# ATmega128RFA1-DevBoard.net
KiCad netlist of a schematic drawn in EAGLE
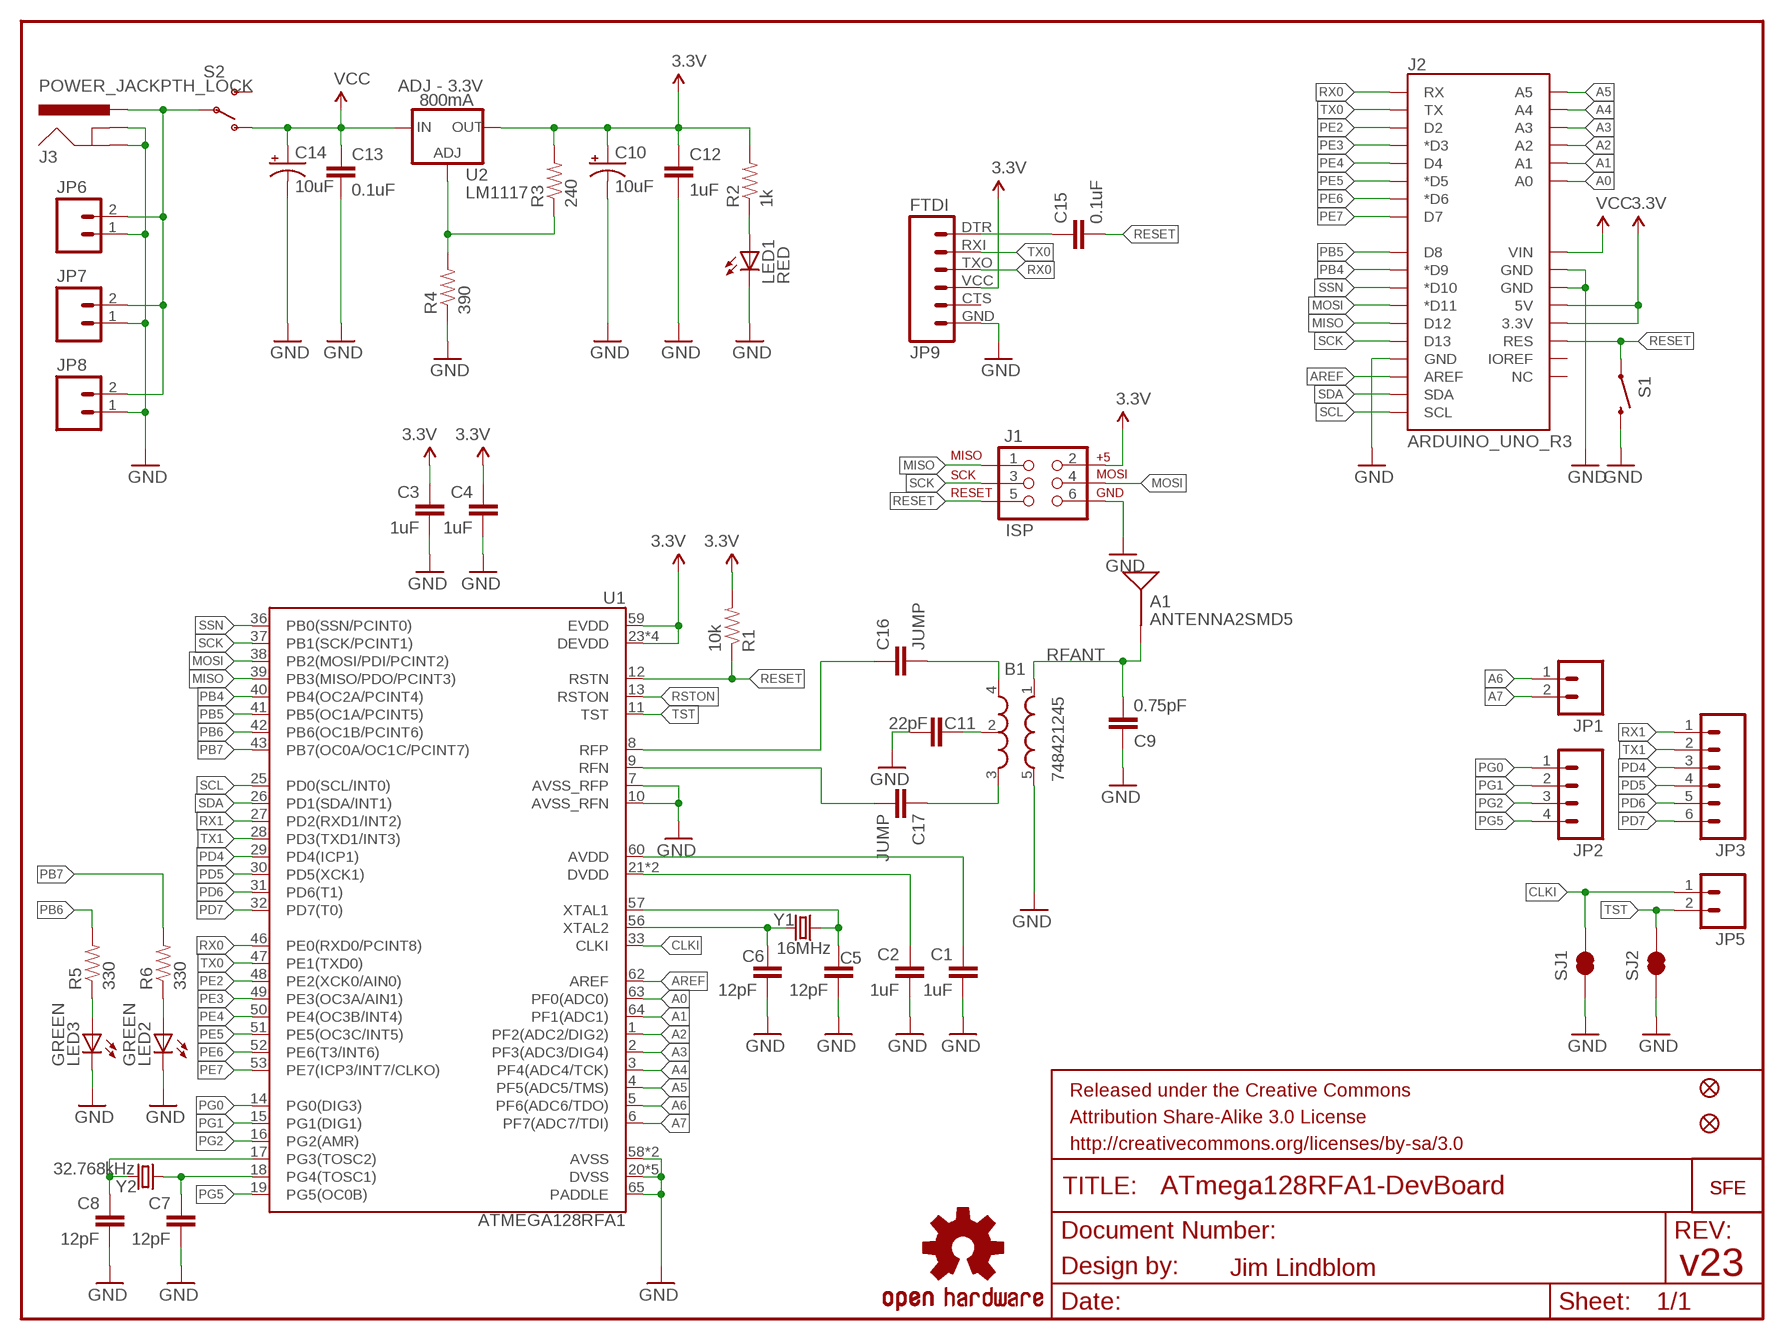
[diagram p0: schematic, sheet 1]

(export (version "E")
  (design (tool "Eeschema 10.0.6"))
  (components
    (comp (ref "A1")
      (value "ANTENNA2SMD5")
      (footprint "eagle-import:ANTENNA-CHIP5")
      (libsource (lib "eagle-import") (part "ANTENNA2SMD5"))
    )
    (comp (ref "B1")
      (value "748421245")
      (footprint "eagle-import:BALUN")
      (libsource (lib "eagle-import") (part "BALUN0805"))
    )
    (comp (ref "C1")
      (value "1uF")
      (footprint "eagle-import:0402-CAP")
      (libsource (lib "eagle-import") (part "SparkFun-Passives_CAP0402-CAP"))
    )
    (comp (ref "C2")
      (value "1uF")
      (footprint "eagle-import:0402-CAP")
      (libsource (lib "eagle-import") (part "SparkFun-Passives_CAP0402-CAP"))
    )
    (comp (ref "C3")
      (value "1uF")
      (footprint "eagle-import:0402-CAP")
      (libsource (lib "eagle-import") (part "SparkFun-Passives_CAP0402-CAP"))
    )
    (comp (ref "C4")
      (value "1uF")
      (footprint "eagle-import:0402-CAP")
      (libsource (lib "eagle-import") (part "SparkFun-Passives_CAP0402-CAP"))
    )
    (comp (ref "C5")
      (value "12pF")
      (footprint "eagle-import:0402-CAP")
      (libsource (lib "eagle-import") (part "SparkFun-Passives_CAP0402-CAP"))
    )
    (comp (ref "C6")
      (value "12pF")
      (footprint "eagle-import:0402-CAP")
      (libsource (lib "eagle-import") (part "SparkFun-Passives_CAP0402-CAP"))
    )
    (comp (ref "C7")
      (value "12pF")
      (footprint "eagle-import:0402-CAP")
      (libsource (lib "eagle-import") (part "SparkFun-Passives_CAP0402-CAP"))
    )
    (comp (ref "C8")
      (value "12pF")
      (footprint "eagle-import:0402-CAP")
      (libsource (lib "eagle-import") (part "SparkFun-Passives_CAP0402-CAP"))
    )
    (comp (ref "C9")
      (value "0.75pF")
      (footprint "eagle-import:0402-CAP")
      (libsource (lib "eagle-import") (part "SparkFun-Passives_CAP0402-CAP"))
    )
    (comp (ref "C10")
      (value "10uF")
      (footprint "eagle-import:EIA3216")
      (libsource (lib "eagle-import") (part "CAP_POL1206"))
    )
    (comp (ref "C11")
      (value "22pF")
      (footprint "eagle-import:0402-CAP")
      (libsource (lib "eagle-import") (part "SparkFun-Passives_CAP0402-CAP"))
    )
    (comp (ref "C12")
      (value "1uF")
      (footprint "eagle-import:0402-CAP")
      (libsource (lib "eagle-import") (part "SparkFun-Passives_CAP0402-CAP"))
    )
    (comp (ref "C13")
      (value "0.1uF")
      (footprint "eagle-import:0402-CAP")
      (libsource (lib "eagle-import") (part "SparkFun-Passives_CAP0402-CAP"))
    )
    (comp (ref "C14")
      (value "10uF")
      (footprint "eagle-import:EIA3216")
      (libsource (lib "eagle-import") (part "CAP_POL1206"))
    )
    (comp (ref "C15")
      (value "0.1uF")
      (footprint "eagle-import:0402-CAP")
      (libsource (lib "eagle-import") (part "SparkFun-Passives_CAP0402-CAP"))
    )
    (comp (ref "C16")
      (value "JUMP")
      (footprint "eagle-import:0402-CAP")
      (libsource (lib "eagle-import") (part "CAP0402-CAP"))
    )
    (comp (ref "C17")
      (value "JUMP")
      (footprint "eagle-import:0402-CAP")
      (libsource (lib "eagle-import") (part "CAP0402-CAP"))
    )
    (comp (ref "FID1")
      (value "FIDUCIALUFIDUCIAL")
      (footprint "eagle-import:MICRO-FIDUCIAL")
      (libsource (lib "eagle-import") (part "FIDUCIALUFIDUCIAL"))
    )
    (comp (ref "FID2")
      (value "FIDUCIALUFIDUCIAL")
      (footprint "eagle-import:MICRO-FIDUCIAL")
      (libsource (lib "eagle-import") (part "FIDUCIALUFIDUCIAL"))
    )
    (comp (ref "J1")
      (value "ISP")
      (footprint "eagle-import:2X3-NS")
      (libsource (lib "eagle-import") (part "AVR_SPI_PRG_6NS"))
    )
    (comp (ref "J2")
      (value "ARDUINO_UNO_R3")
      (footprint "eagle-import:ARDUINO_UNO_R3")
      (libsource (lib "eagle-import") (part "ARDUINO_UNO_R3"))
    )
    (comp (ref "J3")
      (value "POWER_JACKPTH_LOCK")
      (footprint "eagle-import:POWER_JACK_PTH_LOCK")
      (libsource (lib "eagle-import") (part "POWER_JACKPTH_LOCK"))
    )
    (comp (ref "JP1")
      (value "M021X02_NO_SILK")
      (footprint "eagle-import:1X02_NO_SILK")
      (libsource (lib "eagle-import") (part "M021X02_NO_SILK"))
    )
    (comp (ref "JP2")
      (value "M041X04_NO_SILK")
      (footprint "eagle-import:1X04_NO_SILK")
      (libsource (lib "eagle-import") (part "M041X04_NO_SILK"))
    )
    (comp (ref "JP3")
      (value "M06SIP-NS")
      (footprint "eagle-import:1X06_NS")
      (libsource (lib "eagle-import") (part "M06SIP-NS"))
    )
    (comp (ref "JP4")
      (value "LOGO-SFENEW")
      (footprint "eagle-import:SFE-NEW-WEBLOGO")
      (libsource (lib "eagle-import") (part "LOGO-SFENEW"))
    )
    (comp (ref "JP5")
      (value "M021X02_NO_SILK")
      (footprint "eagle-import:1X02_NO_SILK")
      (libsource (lib "eagle-import") (part "M021X02_NO_SILK"))
    )
    (comp (ref "JP6")
      (value "M02JST-PTH-2")
      (footprint "eagle-import:JST-2-PTH")
      (libsource (lib "eagle-import") (part "M02JST-PTH-2"))
    )
    (comp (ref "JP7")
      (value "M021X02_NO_SILK")
      (footprint "eagle-import:1X02_NO_SILK")
      (libsource (lib "eagle-import") (part "M021X02_NO_SILK"))
    )
    (comp (ref "JP8")
      (value "M023.5MM-NO_SILK")
      (footprint "eagle-import:SCREWTERMINAL-3.5MM-2-NS")
      (libsource (lib "eagle-import") (part "M023.5MM-NO_SILK"))
    )
    (comp (ref "JP9")
      (value "FTDI")
      (footprint "eagle-import:FTDI_BASIC")
      (libsource (lib "eagle-import") (part "FTDI_BASICPTH"))
    )
    (comp (ref "JP10")
      (value "LOGO-SFENEW")
      (footprint "eagle-import:SFE-NEW-WEBLOGO")
      (libsource (lib "eagle-import") (part "LOGO-SFENEW"))
    )
    (comp (ref "LED1")
      (value "RED")
      (footprint "eagle-import:LED-0603")
      (libsource (lib "eagle-import") (part "LED0603"))
    )
    (comp (ref "LED2")
      (value "GREEN")
      (footprint "eagle-import:LED-0603")
      (libsource (lib "eagle-import") (part "LED0603"))
    )
    (comp (ref "LED3")
      (value "GREEN")
      (footprint "eagle-import:LED-0603")
      (libsource (lib "eagle-import") (part "LED0603"))
    )
    (comp (ref "R1")
      (value "10k")
      (footprint "eagle-import:0402-RES")
      (libsource (lib "eagle-import") (part "SparkFun-Passives_RESISTOR0402-RES"))
    )
    (comp (ref "R2")
      (value "1k")
      (footprint "eagle-import:0402-RES")
      (libsource (lib "eagle-import") (part "SparkFun-Passives_RESISTOR0402-RES"))
    )
    (comp (ref "R3")
      (value "240")
      (footprint "eagle-import:0402-RES")
      (libsource (lib "eagle-import") (part "RESISTOR0402-RES"))
    )
    (comp (ref "R4")
      (value "390")
      (footprint "eagle-import:0402-RES")
      (libsource (lib "eagle-import") (part "RESISTOR0402-RES"))
    )
    (comp (ref "R5")
      (value "330")
      (footprint "eagle-import:0402-RES")
      (libsource (lib "eagle-import") (part "RESISTOR0402-RES"))
    )
    (comp (ref "R6")
      (value "330")
      (footprint "eagle-import:0402-RES")
      (libsource (lib "eagle-import") (part "RESISTOR0402-RES"))
    )
    (comp (ref "S1")
      (value "SWITCH-MOMENTARY-2SMD")
      (footprint "eagle-import:TACTILE_SWITCH_SMD")
      (libsource (lib "eagle-import") (part "SWITCH-MOMENTARY-2SMD"))
    )
    (comp (ref "S2")
      (value "SWITCH-SPST-SMD-A")
      (footprint "eagle-import:SWITCH-SPST-SMD-A")
      (libsource (lib "eagle-import") (part "SWITCH-SPST-SMD-A"))
    )
    (comp (ref "SJ1")
      (value "SOLDERJUMPERTRACE")
      (footprint "eagle-import:SJ_2S-TRACE")
      (libsource (lib "eagle-import") (part "SOLDERJUMPERTRACE"))
    )
    (comp (ref "SJ2")
      (value "SOLDERJUMPERTRACE")
      (footprint "eagle-import:SJ_2S-TRACE")
      (libsource (lib "eagle-import") (part "SOLDERJUMPERTRACE"))
    )
    (comp (ref "U$1")
      (value "OSHW-LOGOS")
      (footprint "eagle-import:OSHW-LOGO-S")
      (libsource (lib "eagle-import") (part "OSHW-LOGOS"))
    )
    (comp (ref "U1")
      (value "ATMEGA128RFA1")
      (footprint "eagle-import:QFN-64")
      (libsource (lib "eagle-import") (part "ATMEGA128RFA1"))
    )
    (comp (ref "U2")
      (value "LM1117")
      (footprint "eagle-import:SOT223")
      (libsource (lib "eagle-import") (part "V_REG_317SMD"))
    )
    (comp (ref "Y1")
      (value "16MHz")
      (footprint "eagle-import:CRYSTAL-SMD-5X3")
      (libsource (lib "eagle-import") (part "CRYSTAL5X3"))
    )
    (comp (ref "Y2")
      (value "32.768kHz")
      (footprint "eagle-import:CRYSTAL-32KHZ-SMD")
      (libsource (lib "eagle-import") (part "CRYSTAL32-SMD"))
    )
  )
  (nets
    (net (code "1") (name "/RFANT") (class "Default")
      (node (ref "A1") (pin "FEED") (pinfunction "SIGNAL_FEED") (pintype "bidirectional"))
      (node (ref "B1") (pin "1") (pinfunction "IN_1") (pintype "bidirectional"))
      (node (ref "C9") (pin "2") (pinfunction "2_2") (pintype "passive"))
    )
    (net (code "2") (name "3.3V") (class "Default")
      (node (ref "C10") (pin "A") (pinfunction "+_A") (pintype "passive"))
      (node (ref "C12") (pin "1") (pinfunction "1_1") (pintype "passive"))
      (node (ref "C3") (pin "1") (pinfunction "1_1") (pintype "passive"))
      (node (ref "C4") (pin "1") (pinfunction "1_1") (pintype "passive"))
      (node (ref "J1") (pin "2") (pinfunction "2_2") (pintype "passive"))
      (node (ref "J2") (pin "3.3V") (pinfunction "3.3V_3.3V") (pintype "bidirectional"))
      (node (ref "J2") (pin "5V") (pinfunction "5V_5V") (pintype "bidirectional"))
      (node (ref "JP9") (pin "VCC") (pinfunction "4_VCC") (pintype "passive"))
      (node (ref "R1") (pin "2") (pinfunction "2_2") (pintype "passive"))
      (node (ref "R2") (pin "2") (pinfunction "2_2") (pintype "passive"))
      (node (ref "R3") (pin "2") (pinfunction "2_2") (pintype "passive"))
      (node (ref "U1") (pin "23") (pinfunction "DEVDD_23") (pintype "bidirectional"))
      (node (ref "U1") (pin "34") (pinfunction "DEVDD_34") (pintype "bidirectional"))
      (node (ref "U1") (pin "44") (pinfunction "DEVDD_44") (pintype "bidirectional"))
      (node (ref "U1") (pin "54") (pinfunction "DEVDD_54") (pintype "bidirectional"))
      (node (ref "U1") (pin "59") (pinfunction "EVDD_59") (pintype "bidirectional"))
      (node (ref "U2") (pin "2") (pinfunction "OUT_2") (pintype "output"))
    )
    (net (code "3") (name "A0") (class "Default")
      (node (ref "J2") (pin "A0") (pinfunction "A0_A0") (pintype "bidirectional"))
      (node (ref "U1") (pin "63") (pinfunction "PF0(ADC0)_63") (pintype "bidirectional"))
    )
    (net (code "4") (name "A1") (class "Default")
      (node (ref "J2") (pin "A1") (pinfunction "A1_A1") (pintype "bidirectional"))
      (node (ref "U1") (pin "64") (pinfunction "PF1(ADC1)_64") (pintype "bidirectional"))
    )
    (net (code "5") (name "A2") (class "Default")
      (node (ref "J2") (pin "A2") (pinfunction "A2_A2") (pintype "bidirectional"))
      (node (ref "U1") (pin "1") (pinfunction "PF2(ADC2/DIG2)_1") (pintype "bidirectional"))
    )
    (net (code "6") (name "A3") (class "Default")
      (node (ref "J2") (pin "A3") (pinfunction "A3_A3") (pintype "bidirectional"))
      (node (ref "U1") (pin "2") (pinfunction "PF3(ADC3/DIG4)_2") (pintype "bidirectional"))
    )
    (net (code "7") (name "A4") (class "Default")
      (node (ref "J2") (pin "A4") (pinfunction "A4_A4") (pintype "bidirectional"))
      (node (ref "U1") (pin "3") (pinfunction "PF4(ADC4/TCK)_3") (pintype "bidirectional"))
    )
    (net (code "8") (name "A5") (class "Default")
      (node (ref "J2") (pin "A5") (pinfunction "A5_A5") (pintype "bidirectional"))
      (node (ref "U1") (pin "4") (pinfunction "PF5(ADC5/TMS)_4") (pintype "bidirectional"))
    )
    (net (code "9") (name "A6") (class "Default")
      (node (ref "JP1") (pin "1") (pinfunction "1_1") (pintype "passive"))
      (node (ref "U1") (pin "5") (pinfunction "PF6(ADC6/TDO)_5") (pintype "bidirectional"))
    )
    (net (code "10") (name "A7") (class "Default")
      (node (ref "JP1") (pin "2") (pinfunction "2_2") (pintype "passive"))
      (node (ref "U1") (pin "6") (pinfunction "PF7(ADC7/TDI)_6") (pintype "bidirectional"))
    )
    (net (code "11") (name "AREF") (class "Default")
      (node (ref "J2") (pin "AREF") (pinfunction "AREF_AREF") (pintype "bidirectional"))
      (node (ref "U1") (pin "62") (pinfunction "AREF_62") (pintype "bidirectional"))
    )
    (net (code "12") (name "CLKI") (class "Default")
      (node (ref "JP5") (pin "1") (pinfunction "1_1") (pintype "passive"))
      (node (ref "SJ1") (pin "2") (pinfunction "2_2") (pintype "passive"))
      (node (ref "U1") (pin "33") (pinfunction "CLKI_33") (pintype "bidirectional"))
    )
    (net (code "13") (name "GND") (class "Default")
      (node (ref "B1") (pin "5") (pinfunction "GND_5") (pintype "bidirectional"))
      (node (ref "C1") (pin "2") (pinfunction "2_2") (pintype "passive"))
      (node (ref "C10") (pin "C") (pinfunction "-_C") (pintype "passive"))
      (node (ref "C11") (pin "2") (pinfunction "2_2") (pintype "passive"))
      (node (ref "C12") (pin "2") (pinfunction "2_2") (pintype "passive"))
      (node (ref "C13") (pin "2") (pinfunction "2_2") (pintype "passive"))
      (node (ref "C14") (pin "C") (pinfunction "-_C") (pintype "passive"))
      (node (ref "C2") (pin "2") (pinfunction "2_2") (pintype "passive"))
      (node (ref "C3") (pin "2") (pinfunction "2_2") (pintype "passive"))
      (node (ref "C4") (pin "2") (pinfunction "2_2") (pintype "passive"))
      (node (ref "C5") (pin "2") (pinfunction "2_2") (pintype "passive"))
      (node (ref "C6") (pin "2") (pinfunction "2_2") (pintype "passive"))
      (node (ref "C7") (pin "2") (pinfunction "2_2") (pintype "passive"))
      (node (ref "C8") (pin "2") (pinfunction "2_2") (pintype "passive"))
      (node (ref "C9") (pin "1") (pinfunction "1_1") (pintype "passive"))
      (node (ref "J1") (pin "6") (pinfunction "6_6") (pintype "passive"))
      (node (ref "J2") (pin "GND@0") (pinfunction "GND_GND@0") (pintype "bidirectional"))
      (node (ref "J2") (pin "GND@1") (pinfunction "GND_GND@1") (pintype "bidirectional"))
      (node (ref "J2") (pin "GND@2") (pinfunction "GND_GND@2") (pintype "bidirectional"))
      (node (ref "J3") (pin "GND") (pinfunction "GND_GND") (pintype "bidirectional"))
      (node (ref "J3") (pin "GNDBREAK") (pinfunction "GNDBREAK_GNDBREAK") (pintype "bidirectional"))
      (node (ref "JP6") (pin "1") (pinfunction "1_1") (pintype "passive"))
      (node (ref "JP7") (pin "1") (pinfunction "1_1") (pintype "passive"))
      (node (ref "JP8") (pin "1") (pinfunction "1_1") (pintype "passive"))
      (node (ref "JP9") (pin "GND") (pinfunction "6_GND") (pintype "passive"))
      (node (ref "LED1") (pin "C") (pinfunction "C_C") (pintype "passive"))
      (node (ref "LED2") (pin "C") (pinfunction "C_C") (pintype "passive"))
      (node (ref "LED3") (pin "C") (pinfunction "C_C") (pintype "passive"))
      (node (ref "R4") (pin "1") (pinfunction "1_1") (pintype "passive"))
      (node (ref "S1") (pin "3") (pinfunction "2_3") (pintype "passive"))
      (node (ref "SJ1") (pin "1") (pinfunction "1_1") (pintype "passive"))
      (node (ref "SJ2") (pin "1") (pinfunction "1_1") (pintype "passive"))
      (node (ref "U1") (pin "10") (pinfunction "AVSS_RFN_10") (pintype "bidirectional"))
      (node (ref "U1") (pin "20") (pinfunction "DVSS_20") (pintype "bidirectional"))
      (node (ref "U1") (pin "24") (pinfunction "DVSS_24") (pintype "bidirectional"))
      (node (ref "U1") (pin "35") (pinfunction "DVSS_35") (pintype "bidirectional"))
      (node (ref "U1") (pin "45") (pinfunction "DVSS_45") (pintype "bidirectional"))
      (node (ref "U1") (pin "55") (pinfunction "DVSS_55") (pintype "bidirectional"))
      (node (ref "U1") (pin "58") (pinfunction "AVSS_58") (pintype "bidirectional"))
      (node (ref "U1") (pin "61") (pinfunction "AVSS_61") (pintype "bidirectional"))
      (node (ref "U1") (pin "65") (pinfunction "PADDLE_65") (pintype "bidirectional"))
      (node (ref "U1") (pin "7") (pinfunction "AVSS_RFP_7") (pintype "bidirectional"))
    )
    (net (code "14") (name "MISO") (class "Default")
      (node (ref "J1") (pin "1") (pinfunction "1_1") (pintype "passive"))
      (node (ref "J2") (pin "D12") (pinfunction "D12_D12") (pintype "bidirectional"))
      (node (ref "U1") (pin "39") (pinfunction "PB3(MISO/PDO/PCINT3)_39") (pintype "bidirectional"))
    )
    (net (code "15") (name "MOSI") (class "Default")
      (node (ref "J1") (pin "4") (pinfunction "4_4") (pintype "passive"))
      (node (ref "J2") (pin "D11") (pinfunction "*D11_D11") (pintype "bidirectional"))
      (node (ref "U1") (pin "38") (pinfunction "PB2(MOSI/PDI/PCINT2)_38") (pintype "bidirectional"))
    )
    (net (code "16") (name "Net-(B1-GND-Pad2)") (class "Default")
      (node (ref "B1") (pin "2") (pinfunction "GND_2") (pintype "bidirectional"))
      (node (ref "C11") (pin "1") (pinfunction "1_1") (pintype "passive"))
    )
    (net (code "17") (name "Net-(B1-OUT1)") (class "Default")
      (node (ref "B1") (pin "4") (pinfunction "OUT1_4") (pintype "bidirectional"))
      (node (ref "C16") (pin "2") (pinfunction "2_2") (pintype "passive"))
    )
    (net (code "18") (name "Net-(B1-OUT2)") (class "Default")
      (node (ref "B1") (pin "3") (pinfunction "OUT2_3") (pintype "bidirectional"))
      (node (ref "C17") (pin "1") (pinfunction "1_1") (pintype "passive"))
    )
    (net (code "19") (name "Net-(C2-Pad1)") (class "Default")
      (node (ref "C2") (pin "1") (pinfunction "1_1") (pintype "passive"))
      (node (ref "U1") (pin "21") (pinfunction "DVDD_21") (pintype "bidirectional"))
      (node (ref "U1") (pin "22") (pinfunction "DVDD_22") (pintype "bidirectional"))
    )
    (net (code "20") (name "Net-(JP9-1)") (class "Default")
      (node (ref "C15") (pin "1") (pinfunction "1_1") (pintype "passive"))
      (node (ref "JP9") (pin "DTR") (pinfunction "1_DTR") (pintype "passive"))
    )
    (net (code "21") (name "Net-(LED1-PadA)") (class "Default")
      (node (ref "LED1") (pin "A") (pinfunction "A_A") (pintype "passive"))
      (node (ref "R2") (pin "1") (pinfunction "1_1") (pintype "passive"))
    )
    (net (code "22") (name "Net-(LED2-PadA)") (class "Default")
      (node (ref "LED2") (pin "A") (pinfunction "A_A") (pintype "passive"))
      (node (ref "R6") (pin "1") (pinfunction "1_1") (pintype "passive"))
    )
    (net (code "23") (name "Net-(LED3-PadA)") (class "Default")
      (node (ref "LED3") (pin "A") (pinfunction "A_A") (pintype "passive"))
      (node (ref "R5") (pin "1") (pinfunction "1_1") (pintype "passive"))
    )
    (net (code "24") (name "Net-(S2-P)") (class "Default")
      (node (ref "J3") (pin "PWR") (pinfunction "PWR_PWR") (pintype "bidirectional"))
      (node (ref "JP6") (pin "2") (pinfunction "2_2") (pintype "passive"))
      (node (ref "JP7") (pin "2") (pinfunction "2_2") (pintype "passive"))
      (node (ref "JP8") (pin "2") (pinfunction "2_2") (pintype "passive"))
      (node (ref "S2") (pin "2") (pinfunction "P_2") (pintype "passive"))
    )
    (net (code "25") (name "Net-(U1-AVDD)") (class "Default")
      (node (ref "C1") (pin "1") (pinfunction "1_1") (pintype "passive"))
      (node (ref "U1") (pin "60") (pinfunction "AVDD_60") (pintype "bidirectional"))
    )
    (net (code "26") (name "Net-(U1-PG3(TOSC2))") (class "Default")
      (node (ref "C8") (pin "1") (pinfunction "1_1") (pintype "passive"))
      (node (ref "U1") (pin "17") (pinfunction "PG3(TOSC2)_17") (pintype "bidirectional"))
      (node (ref "Y2") (pin "X2") (pinfunction "2_X2") (pintype "passive"))
    )
    (net (code "27") (name "Net-(U1-PG4(TOSC1))") (class "Default")
      (node (ref "C7") (pin "1") (pinfunction "1_1") (pintype "passive"))
      (node (ref "U1") (pin "18") (pinfunction "PG4(TOSC1)_18") (pintype "bidirectional"))
      (node (ref "Y2") (pin "X1") (pinfunction "1_X1") (pintype "passive"))
    )
    (net (code "28") (name "Net-(U1-RFN)") (class "Default")
      (node (ref "C17") (pin "2") (pinfunction "2_2") (pintype "passive"))
      (node (ref "U1") (pin "9") (pinfunction "RFN_9") (pintype "bidirectional"))
    )
    (net (code "29") (name "Net-(U1-RFP)") (class "Default")
      (node (ref "C16") (pin "1") (pinfunction "1_1") (pintype "passive"))
      (node (ref "U1") (pin "8") (pinfunction "RFP_8") (pintype "bidirectional"))
    )
    (net (code "30") (name "Net-(U1-XTAL1)") (class "Default")
      (node (ref "C5") (pin "1") (pinfunction "1_1") (pintype "passive"))
      (node (ref "U1") (pin "57") (pinfunction "XTAL1_57") (pintype "bidirectional"))
      (node (ref "Y1") (pin "3") (pinfunction "2_3") (pintype "passive"))
    )
    (net (code "31") (name "Net-(U1-XTAL2)") (class "Default")
      (node (ref "C6") (pin "1") (pinfunction "1_1") (pintype "passive"))
      (node (ref "U1") (pin "56") (pinfunction "XTAL2_56") (pintype "bidirectional"))
      (node (ref "Y1") (pin "1") (pinfunction "1_1") (pintype "passive"))
    )
    (net (code "32") (name "Net-(U2-ADJ)") (class "Default")
      (node (ref "R3") (pin "1") (pinfunction "1_1") (pintype "passive"))
      (node (ref "R4") (pin "2") (pinfunction "2_2") (pintype "passive"))
      (node (ref "U2") (pin "1") (pinfunction "ADJ_1") (pintype "input"))
    )
    (net (code "33") (name "PB4") (class "Default")
      (node (ref "J2") (pin "D9") (pinfunction "*D9_D9") (pintype "bidirectional"))
      (node (ref "U1") (pin "40") (pinfunction "PB4(OC2A/PCINT4)_40") (pintype "bidirectional"))
    )
    (net (code "34") (name "PB5") (class "Default")
      (node (ref "J2") (pin "D8") (pinfunction "D8_D8") (pintype "bidirectional"))
      (node (ref "U1") (pin "41") (pinfunction "PB5(OC1A/PCINT5)_41") (pintype "bidirectional"))
    )
    (net (code "35") (name "PB6") (class "Default")
      (node (ref "R5") (pin "2") (pinfunction "2_2") (pintype "passive"))
      (node (ref "U1") (pin "42") (pinfunction "PB6(OC1B/PCINT6)_42") (pintype "bidirectional"))
    )
    (net (code "36") (name "PB7") (class "Default")
      (node (ref "R6") (pin "2") (pinfunction "2_2") (pintype "passive"))
      (node (ref "U1") (pin "43") (pinfunction "PB7(OC0A/OC1C/PCINT7)_43") (pintype "bidirectional"))
    )
    (net (code "37") (name "PD4") (class "Default")
      (node (ref "JP3") (pin "3") (pinfunction "3_3") (pintype "passive"))
      (node (ref "U1") (pin "29") (pinfunction "PD4(ICP1)_29") (pintype "bidirectional"))
    )
    (net (code "38") (name "PD5") (class "Default")
      (node (ref "JP3") (pin "4") (pinfunction "4_4") (pintype "passive"))
      (node (ref "U1") (pin "30") (pinfunction "PD5(XCK1)_30") (pintype "bidirectional"))
    )
    (net (code "39") (name "PD6") (class "Default")
      (node (ref "JP3") (pin "5") (pinfunction "5_5") (pintype "passive"))
      (node (ref "U1") (pin "31") (pinfunction "PD6(T1)_31") (pintype "bidirectional"))
    )
    (net (code "40") (name "PD7") (class "Default")
      (node (ref "JP3") (pin "6") (pinfunction "6_6") (pintype "passive"))
      (node (ref "U1") (pin "32") (pinfunction "PD7(T0)_32") (pintype "bidirectional"))
    )
    (net (code "41") (name "PE2") (class "Default")
      (node (ref "J2") (pin "D2") (pinfunction "D2_D2") (pintype "bidirectional"))
      (node (ref "U1") (pin "48") (pinfunction "PE2(XCK0/AIN0)_48") (pintype "bidirectional"))
    )
    (net (code "42") (name "PE3") (class "Default")
      (node (ref "J2") (pin "D3") (pinfunction "*D3_D3") (pintype "bidirectional"))
      (node (ref "U1") (pin "49") (pinfunction "PE3(OC3A/AIN1)_49") (pintype "bidirectional"))
    )
    (net (code "43") (name "PE4") (class "Default")
      (node (ref "J2") (pin "D4") (pinfunction "D4_D4") (pintype "bidirectional"))
      (node (ref "U1") (pin "50") (pinfunction "PE4(OC3B/INT4)_50") (pintype "bidirectional"))
    )
    (net (code "44") (name "PE5") (class "Default")
      (node (ref "J2") (pin "D5") (pinfunction "*D5_D5") (pintype "bidirectional"))
      (node (ref "U1") (pin "51") (pinfunction "PE5(OC3C/INT5)_51") (pintype "bidirectional"))
    )
    (net (code "45") (name "PE6") (class "Default")
      (node (ref "J2") (pin "D6") (pinfunction "*D6_D6") (pintype "bidirectional"))
      (node (ref "U1") (pin "52") (pinfunction "PE6(T3/INT6)_52") (pintype "bidirectional"))
    )
    (net (code "46") (name "PE7") (class "Default")
      (node (ref "J2") (pin "D7") (pinfunction "D7_D7") (pintype "bidirectional"))
      (node (ref "U1") (pin "53") (pinfunction "PE7(ICP3/INT7/CLKO)_53") (pintype "bidirectional"))
    )
    (net (code "47") (name "PG0") (class "Default")
      (node (ref "JP2") (pin "1") (pinfunction "1_1") (pintype "passive"))
      (node (ref "U1") (pin "14") (pinfunction "PG0(DIG3)_14") (pintype "bidirectional"))
    )
    (net (code "48") (name "PG1") (class "Default")
      (node (ref "JP2") (pin "2") (pinfunction "2_2") (pintype "passive"))
      (node (ref "U1") (pin "15") (pinfunction "PG1(DIG1)_15") (pintype "bidirectional"))
    )
    (net (code "49") (name "PG2") (class "Default")
      (node (ref "JP2") (pin "3") (pinfunction "3_3") (pintype "passive"))
      (node (ref "U1") (pin "16") (pinfunction "PG2(AMR)_16") (pintype "bidirectional"))
    )
    (net (code "50") (name "PG5") (class "Default")
      (node (ref "JP2") (pin "4") (pinfunction "4_4") (pintype "passive"))
      (node (ref "U1") (pin "19") (pinfunction "PG5(OC0B)_19") (pintype "bidirectional"))
    )
    (net (code "51") (name "RESET") (class "Default")
      (node (ref "C15") (pin "2") (pinfunction "2_2") (pintype "passive"))
      (node (ref "J1") (pin "5") (pinfunction "5_5") (pintype "passive"))
      (node (ref "J2") (pin "RES") (pinfunction "RES_RES") (pintype "bidirectional"))
      (node (ref "R1") (pin "1") (pinfunction "1_1") (pintype "passive"))
      (node (ref "S1") (pin "1") (pinfunction "1_1") (pintype "passive"))
      (node (ref "U1") (pin "12") (pinfunction "RSTN_12") (pintype "bidirectional"))
    )
    (net (code "52") (name "RSTON") (class "Default")
      (node (ref "U1") (pin "13") (pinfunction "RSTON_13") (pintype "bidirectional"))
    )
    (net (code "53") (name "RX0") (class "Default")
      (node (ref "J2") (pin "RX") (pinfunction "RX_RX") (pintype "bidirectional"))
      (node (ref "JP9") (pin "TXO") (pinfunction "3_TXO") (pintype "passive"))
      (node (ref "U1") (pin "46") (pinfunction "PE0(RXD0/PCINT8)_46") (pintype "bidirectional"))
    )
    (net (code "54") (name "RX1") (class "Default")
      (node (ref "JP3") (pin "1") (pinfunction "1_1") (pintype "passive"))
      (node (ref "U1") (pin "27") (pinfunction "PD2(RXD1/INT2)_27") (pintype "bidirectional"))
    )
    (net (code "55") (name "SCK") (class "Default")
      (node (ref "J1") (pin "3") (pinfunction "3_3") (pintype "passive"))
      (node (ref "J2") (pin "D13") (pinfunction "D13_D13") (pintype "bidirectional"))
      (node (ref "U1") (pin "37") (pinfunction "PB1(SCK/PCINT1)_37") (pintype "bidirectional"))
    )
    (net (code "56") (name "SCL") (class "Default")
      (node (ref "J2") (pin "SCL") (pinfunction "SCL_SCL") (pintype "bidirectional"))
      (node (ref "U1") (pin "25") (pinfunction "PD0(SCL/INT0)_25") (pintype "bidirectional"))
    )
    (net (code "57") (name "SDA") (class "Default")
      (node (ref "J2") (pin "SDA") (pinfunction "SDA_SDA") (pintype "bidirectional"))
      (node (ref "U1") (pin "26") (pinfunction "PD1(SDA/INT1)_26") (pintype "bidirectional"))
    )
    (net (code "58") (name "SSN") (class "Default")
      (node (ref "J2") (pin "D10") (pinfunction "*D10_D10") (pintype "bidirectional"))
      (node (ref "U1") (pin "36") (pinfunction "PB0(SSN/PCINT0)_36") (pintype "bidirectional"))
    )
    (net (code "59") (name "TST") (class "Default")
      (node (ref "JP5") (pin "2") (pinfunction "2_2") (pintype "passive"))
      (node (ref "SJ2") (pin "2") (pinfunction "2_2") (pintype "passive"))
      (node (ref "U1") (pin "11") (pinfunction "TST_11") (pintype "bidirectional"))
    )
    (net (code "60") (name "TX0") (class "Default")
      (node (ref "J2") (pin "TX") (pinfunction "TX_TX") (pintype "bidirectional"))
      (node (ref "JP9") (pin "RXI") (pinfunction "2_RXI") (pintype "passive"))
      (node (ref "U1") (pin "47") (pinfunction "PE1(TXD0)_47") (pintype "bidirectional"))
    )
    (net (code "61") (name "TX1") (class "Default")
      (node (ref "JP3") (pin "2") (pinfunction "2_2") (pintype "passive"))
      (node (ref "U1") (pin "28") (pinfunction "PD3(TXD1/INT3)_28") (pintype "bidirectional"))
    )
    (net (code "62") (name "VCC") (class "Default")
      (node (ref "C13") (pin "1") (pinfunction "1_1") (pintype "passive"))
      (node (ref "C14") (pin "A") (pinfunction "+_A") (pintype "passive"))
      (node (ref "J2") (pin "VIN") (pinfunction "VIN_VIN") (pintype "bidirectional"))
      (node (ref "S2") (pin "1") (pinfunction "O_1") (pintype "passive"))
      (node (ref "U2") (pin "3") (pinfunction "IN_3") (pintype "input"))
    )
    (net (code "63") (name "unconnected-(J2-PadIOREF)") (class "Default")
      (node (ref "J2") (pin "IOREF") (pinfunction "IOREF_IOREF") (pintype "bidirectional"))
    )
    (net (code "64") (name "unconnected-(J2-PadNC)") (class "Default")
      (node (ref "J2") (pin "NC") (pinfunction "NC_NC") (pintype "bidirectional"))
    )
    (net (code "65") (name "unconnected-(JP9-5-PadCTS)") (class "Default")
      (node (ref "JP9") (pin "CTS") (pinfunction "5_CTS") (pintype "passive"))
    )
    (net (code "66") (name "unconnected-(S2-S-Pad3)") (class "Default")
      (node (ref "S2") (pin "3") (pinfunction "S_3") (pintype "passive"))
    )
  )
)
